# Nets_Acelerometro.net
KiCad netlist of a schematic drawn in Altium Designer
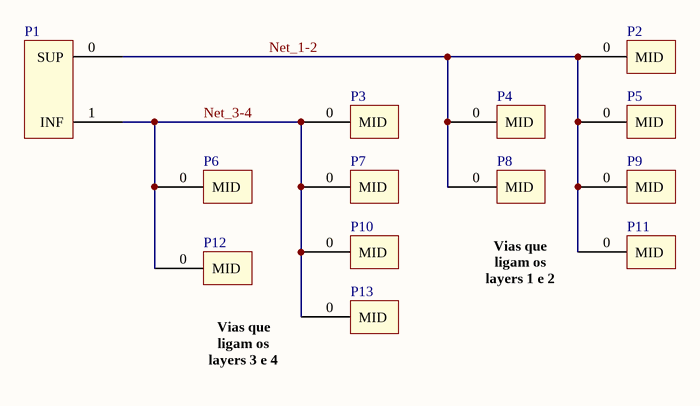
[diagram p0: Nets_Acelerometro.SchDoc]

(export (version "E")
  (design (tool "Eeschema 10.0.6"))
  (components
    (comp (ref "P1")
      (value "Pino de saida de dados")
      (footprint "SAIDA_DADOS")
      (libsource (lib "Biblioteca_Squematico") (part "Pin_Duplo"))
    )
    (comp (ref "P2")
      (value "Via para conectar")
      (footprint "Via_Conect")
      (libsource (lib "Biblioteca_Squematico") (part "Pin_Conect"))
    )
    (comp (ref "P3")
      (value "Via para conectar")
      (footprint "Via_Conect")
      (libsource (lib "Biblioteca_Squematico") (part "Pin_Conect"))
    )
    (comp (ref "P4")
      (value "Via para conectar")
      (footprint "Via_Conect")
      (libsource (lib "Biblioteca_Squematico") (part "Pin_Conect"))
    )
    (comp (ref "P5")
      (value "Via para conectar")
      (footprint "Via_Conect")
      (libsource (lib "Biblioteca_Squematico") (part "Pin_Conect"))
    )
    (comp (ref "P6")
      (value "Via para conectar")
      (footprint "Via_Conect")
      (libsource (lib "Biblioteca_Squematico") (part "Pin_Conect"))
    )
    (comp (ref "P7")
      (value "Via para conectar")
      (footprint "Via_Conect")
      (libsource (lib "Biblioteca_Squematico") (part "Pin_Conect"))
    )
    (comp (ref "P8")
      (value "Via para conectar")
      (footprint "Via_Conect")
      (libsource (lib "Biblioteca_Squematico") (part "Pin_Conect"))
    )
    (comp (ref "P9")
      (value "Via para conectar")
      (footprint "Via_Conect")
      (libsource (lib "Biblioteca_Squematico") (part "Pin_Conect"))
    )
    (comp (ref "P10")
      (value "Via para conectar")
      (footprint "Via_Conect")
      (libsource (lib "Biblioteca_Squematico") (part "Pin_Conect"))
    )
    (comp (ref "P11")
      (value "Via para conectar")
      (footprint "Via_Conect")
      (libsource (lib "Biblioteca_Squematico") (part "Pin_Conect"))
    )
    (comp (ref "P12")
      (value "Via para conectar")
      (footprint "Via_Conect")
      (libsource (lib "Biblioteca_Squematico") (part "Pin_Conect"))
    )
    (comp (ref "P13")
      (value "Via para conectar")
      (footprint "Via_Conect")
      (libsource (lib "Biblioteca_Squematico") (part "Pin_Conect"))
    )
  )
  (nets
    (net (code "1") (name "/Net_1-2") (class "Default")
      (node (ref "P1") (pin "0") (pinfunction "SUP_0") (pintype "passive"))
      (node (ref "P11") (pin "0") (pinfunction "MID_0") (pintype "passive"))
      (node (ref "P2") (pin "0") (pinfunction "MID_0") (pintype "passive"))
      (node (ref "P4") (pin "0") (pinfunction "MID_0") (pintype "passive"))
      (node (ref "P5") (pin "0") (pinfunction "MID_0") (pintype "passive"))
      (node (ref "P8") (pin "0") (pinfunction "MID_0") (pintype "passive"))
      (node (ref "P9") (pin "0") (pinfunction "MID_0") (pintype "passive"))
    )
    (net (code "2") (name "/Net_3-4") (class "Default")
      (node (ref "P1") (pin "1") (pinfunction "INF_1") (pintype "passive"))
      (node (ref "P10") (pin "0") (pinfunction "MID_0") (pintype "passive"))
      (node (ref "P12") (pin "0") (pinfunction "MID_0") (pintype "passive"))
      (node (ref "P13") (pin "0") (pinfunction "MID_0") (pintype "passive"))
      (node (ref "P3") (pin "0") (pinfunction "MID_0") (pintype "passive"))
      (node (ref "P6") (pin "0") (pinfunction "MID_0") (pintype "passive"))
      (node (ref "P7") (pin "0") (pinfunction "MID_0") (pintype "passive"))
    )
  )
)
